# loom-charging-cart.net
KiCad netlist of a schematic drawn in Altium Designer
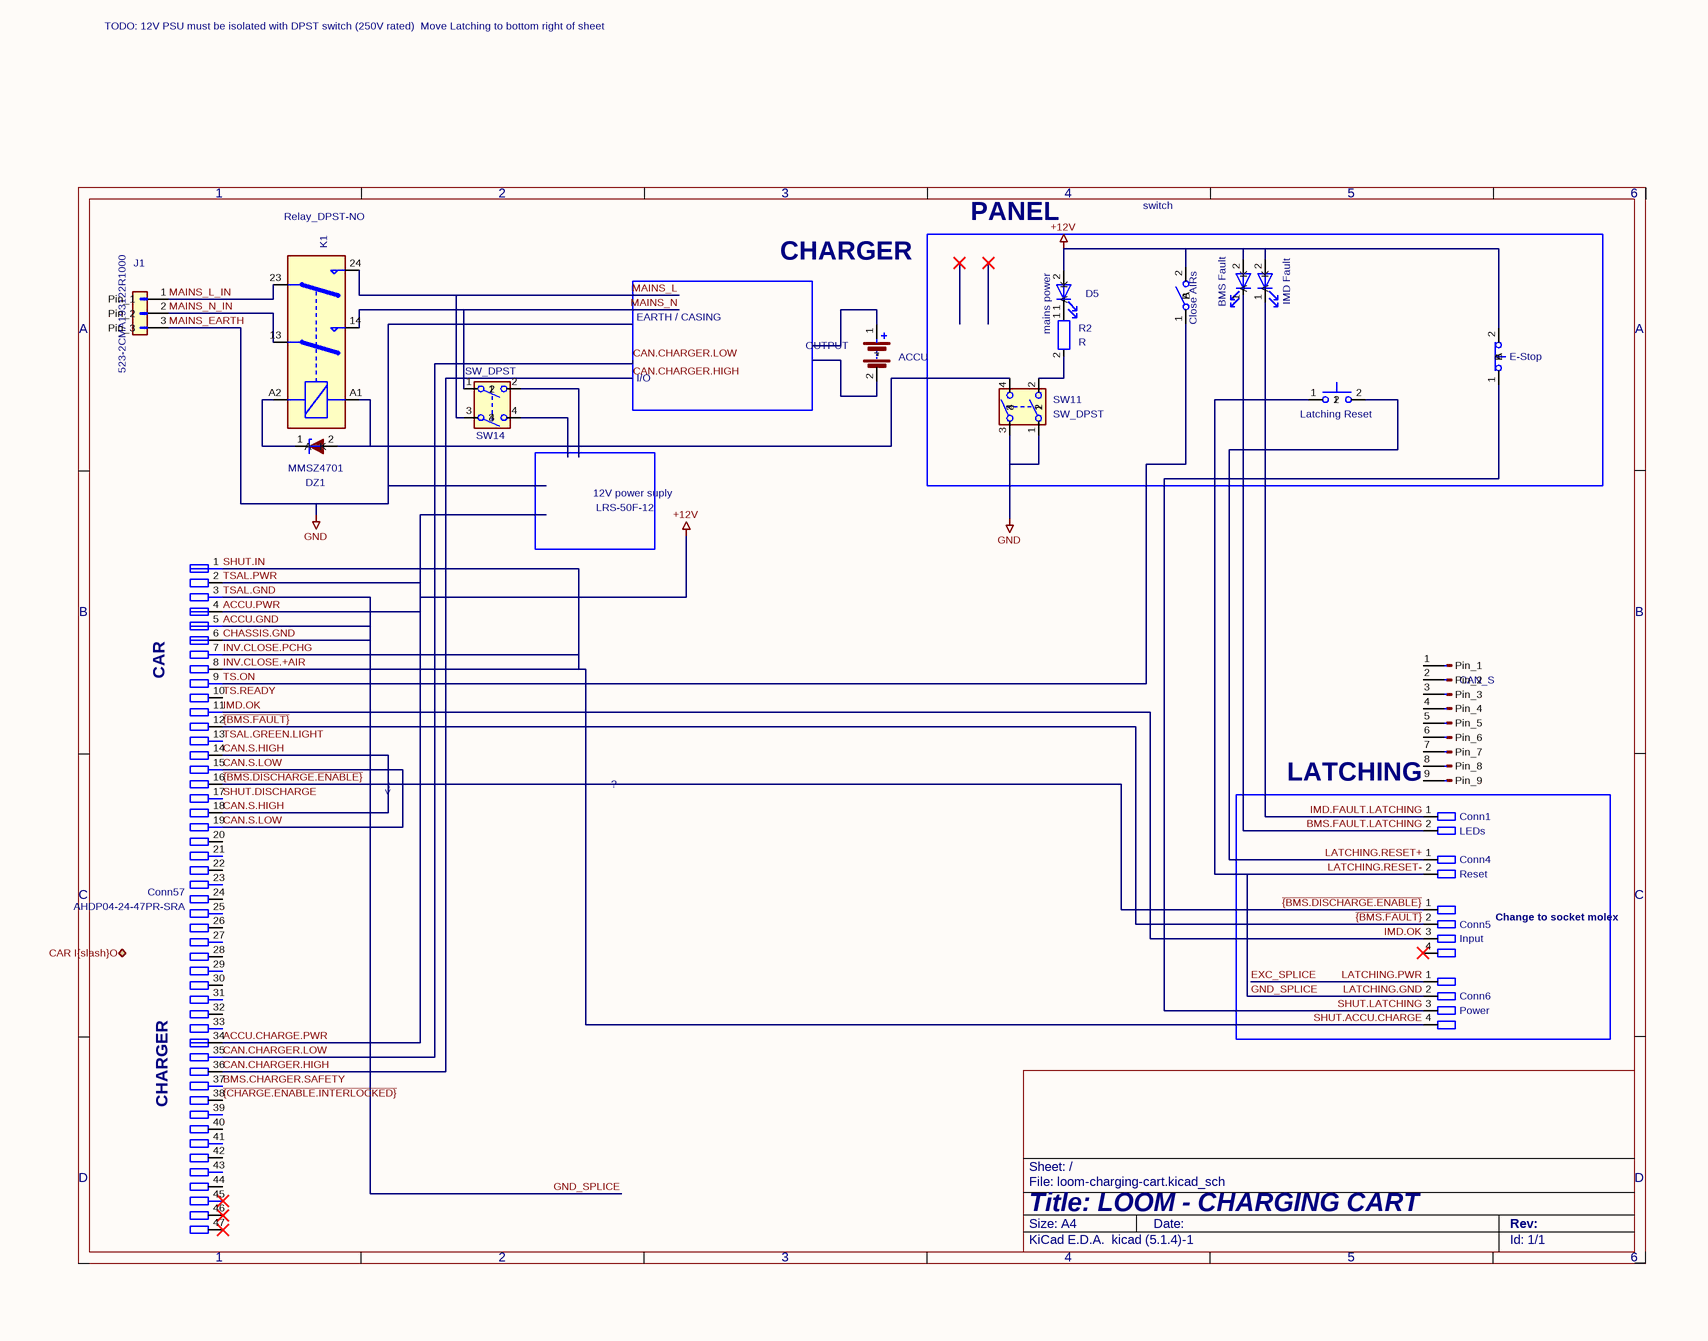
[diagram p0: loom-charging-cart.SchDoc]

(export (version "E")
  (design (tool "Eeschema 10.0.6"))
  (components
    (comp (ref "BT1")
      (value "ACCU")
      (description "Multiple-cell battery")
      (libsource (lib "Device") (part "Battery"))
    )
    (comp (ref "Conn1")
      (value "Molex_2x1P_Horizontal_THT")
      (fields (field (name "NAME") "LEDs"))
      (libsource (lib "Connectors_SUFST") (part "Molex_2x1P_Horizontal_THT"))
    )
    (comp (ref "Conn4")
      (value "Molex_2x1P_Horizontal_THT")
      (fields (field (name "NAME") "Reset"))
      (libsource (lib "Connectors_SUFST") (part "Molex_2x1P_Horizontal_THT"))
    )
    (comp (ref "Conn5")
      (value "Molex_2x2P_Horizontal")
      (fields (field (name "NAME") "Input"))
      (libsource (lib "Connectors_SUFST") (part "Molex_2x2P_Horizontal"))
    )
    (comp (ref "Conn6")
      (value "Molex_2x2P_Horizontal")
      (fields (field (name "NAME") "Power"))
      (libsource (lib "Connectors_SUFST") (part "Molex_2x2P_Horizontal"))
    )
    (comp (ref "Conn57")
      (value "AMPHENOL-47P-Pannel")
      (fields (field (name "P/N") "AHDP04-24-47PR-SRA"))
      (libsource (lib "Connectors_SUFST") (part "AMPHENOL-47P-Pannel"))
    )
    (comp (ref "D1")
      (value "IMD Fault")
      (description "Light emitting diode")
      (libsource (lib "Device") (part "LED"))
    )
    (comp (ref "D2")
      (value "BMS Fault")
      (description "Light emitting diode")
      (libsource (lib "Device") (part "LED"))
    )
    (comp (ref "D5")
      (value "mains power")
      (description "Light emitting diode")
      (libsource (lib "*") (part "LED_1"))
    )
    (comp (ref "DZ1")
      (value "MMSZ4701")
      (footprint "D_SOD-123")
      (description "SOD-123 Zener diode, 14V, 500mW, Alternate KiCAD Library")
      (libsource (lib "PCM_Diode_Zener_AKL") (part "MMSZ4701"))
    )
    (comp (ref "J1") (value "523-2CMA193122R1000") (libsource (lib "Connector_Generic") (part "Conn_01x03")))
    (comp (ref "J2")
      (value "CAN_S")
      (description "Generic connector, single row, 01x09, script generated")
      (libsource (lib "Connector") (part "Conn_01x09_Pin"))
    )
    (comp (ref "K1")
      (value "Relay_DPST-NO")
      (description "Monostable Relay DPST, Normally Open, EN50005")
      (libsource (lib "Relay") (part "Relay_DPST-NO"))
    )
    (comp (ref "R2") (value "R") (description "Resistor") (libsource (lib "Device") (part "R")))
    (comp (ref "SW1") (value "E-Stop") (libsource (lib "Switch") (part "SW_Push_Open")))
    (comp (ref "SW2")
      (value "Latching Reset")
      (description "Push button switch, generic, two pins")
      (libsource (lib "Switch") (part "SW_Push"))
    )
    (comp (ref "SW3")
      (value "Close AIRs")
      (description "Single Pole Single Throw (SPST) switch")
      (libsource (lib "Switch") (part "SW_SPST"))
    )
    (comp (ref "SW11")
      (value "SW_DPST")
      (description "Double Pole Single Throw (DPST) Switch")
      (libsource (lib "Switch") (part "SW_DPST"))
    )
    (comp (ref "SW14")
      (value "SW_DPST")
      (description "Double Pole Single Throw (DPST) Switch")
      (libsource (lib "Switch") (part "SW_DPST"))
    )
  )
  (nets
    (net (code "1") (name "+12V") (class "Default")
      (node (ref "Conn57") (pin "2") (pinfunction "2_2") (pintype "passive"))
      (node (ref "Conn57") (pin "34") (pinfunction "34_34") (pintype "passive"))
      (node (ref "Conn57") (pin "4") (pinfunction "4_4") (pintype "passive"))
      (node (ref "D1") (pin "2") (pinfunction "A_2") (pintype "passive"))
      (node (ref "D2") (pin "2") (pinfunction "A_2") (pintype "passive"))
      (node (ref "D5") (pin "2") (pinfunction "A_2") (pintype "passive"))
      (node (ref "SW1") (pin "2") (pinfunction "B_2") (pintype "passive"))
      (node (ref "SW3") (pin "2") (pinfunction "B_2") (pintype "passive"))
    )
    (net (code "2") (name "/ACCU.GND") (class "Default")
      (node (ref "Conn4") (pin "2") (pinfunction "2_2") (pintype "passive"))
      (node (ref "Conn57") (pin "3") (pinfunction "3_3") (pintype "passive"))
      (node (ref "Conn57") (pin "5") (pinfunction "5_5") (pintype "passive"))
      (node (ref "Conn57") (pin "6") (pinfunction "6_6") (pintype "passive"))
      (node (ref "Conn6") (pin "2") (pinfunction "2_2") (pintype "passive"))
      (node (ref "SW2") (pin "1") (pinfunction "1_1") (pintype "passive"))
    )
    (net (code "3") (name "/BMS.CHARGER.SAFETY") (class "Default")
      (node (ref "Conn57") (pin "37") (pinfunction "37_37") (pintype "passive"))
    )
    (net (code "4") (name "/BMS.FAULT.LATCHING") (class "Default")
      (node (ref "Conn1") (pin "2") (pinfunction "2_2") (pintype "passive"))
      (node (ref "D2") (pin "1") (pinfunction "K_1") (pintype "passive"))
    )
    (net (code "5") (name "/CAN.CHARGER.HIGH") (class "Default")
      (node (ref "Conn57") (pin "36") (pinfunction "36_36") (pintype "passive"))
    )
    (net (code "6") (name "/CAN.CHARGER.LOW") (class "Default")
      (node (ref "Conn57") (pin "35") (pinfunction "35_35") (pintype "passive"))
    )
    (net (code "7") (name "/CAN.S.HIGH") (class "Default")
      (node (ref "Conn57") (pin "14") (pinfunction "14_14") (pintype "passive"))
      (node (ref "Conn57") (pin "18") (pinfunction "18_18") (pintype "passive"))
    )
    (net (code "8") (name "/CAN.S.LOW") (class "Default")
      (node (ref "Conn57") (pin "15") (pinfunction "15_15") (pintype "passive"))
      (node (ref "Conn57") (pin "19") (pinfunction "19_19") (pintype "passive"))
    )
    (net (code "10") (name "/EXC_SPLICE") (class "Default")
      (node (ref "Conn6") (pin "1") (pinfunction "1_1") (pintype "passive"))
    )
    (net (code "11") (name "/IMD.FAULT.LATCHING") (class "Default")
      (node (ref "Conn1") (pin "1") (pinfunction "1_1") (pintype "passive"))
      (node (ref "D1") (pin "1") (pinfunction "K_1") (pintype "passive"))
    )
    (net (code "12") (name "/IMD.OK") (class "Default")
      (node (ref "Conn5") (pin "3") (pinfunction "3_3") (pintype "passive"))
      (node (ref "Conn57") (pin "11") (pinfunction "11_11") (pintype "passive"))
    )
    (net (code "13") (name "/INV.CLOSE.+AIR") (class "Default")
      (node (ref "Conn57") (pin "1") (pinfunction "1_1") (pintype "passive"))
      (node (ref "Conn57") (pin "7") (pinfunction "7_7") (pintype "passive"))
      (node (ref "Conn57") (pin "8") (pinfunction "8_8") (pintype "passive"))
      (node (ref "Conn6") (pin "4") (pinfunction "4_4") (pintype "passive"))
    )
    (net (code "14") (name "/LATCHING.RESET+") (class "Default")
      (node (ref "Conn4") (pin "1") (pinfunction "1_1") (pintype "passive"))
      (node (ref "SW2") (pin "2") (pinfunction "2_2") (pintype "passive"))
    )
    (net (code "15") (name "/MAINS_L") (class "Default")
      (node (ref "K1") (pin "24") (pinfunction "24_24") (pintype "passive"))
      (node (ref "SW14") (pin "3") (pinfunction "3_3") (pintype "passive"))
    )
    (net (code "16") (name "/MAINS_L_IN") (class "Default")
      (node (ref "J1") (pin "1") (pinfunction "Pin_1_1") (pintype "passive"))
      (node (ref "K1") (pin "23") (pinfunction "23_23") (pintype "passive"))
    )
    (net (code "17") (name "/MAINS_N") (class "Default")
      (node (ref "K1") (pin "14") (pinfunction "14_14") (pintype "passive"))
      (node (ref "SW14") (pin "1") (pinfunction "1_1") (pintype "passive"))
    )
    (net (code "18") (name "/MAINS_N_IN") (class "Default")
      (node (ref "J1") (pin "2") (pinfunction "Pin_2_2") (pintype "passive"))
      (node (ref "K1") (pin "13") (pinfunction "13_13") (pintype "passive"))
    )
    (net (code "19") (name "/SHUT.DISCHARGE") (class "Default")
      (node (ref "Conn57") (pin "17") (pinfunction "17_17") (pintype "passive"))
    )
    (net (code "20") (name "/SHUT.LATCHING") (class "Default")
      (node (ref "Conn6") (pin "3") (pinfunction "3_3") (pintype "passive"))
      (node (ref "SW1") (pin "1") (pinfunction "A_1") (pintype "passive"))
    )
    (net (code "21") (name "/TS.ON") (class "Default")
      (node (ref "Conn57") (pin "9") (pinfunction "9_9") (pintype "passive"))
      (node (ref "SW3") (pin "1") (pinfunction "A_1") (pintype "passive"))
    )
    (net (code "22") (name "/TS.READY") (class "Default")
      (node (ref "Conn57") (pin "10") (pinfunction "10_10") (pintype "passive"))
    )
    (net (code "23") (name "/TSAL.GREEN.LIGHT") (class "Default")
      (node (ref "Conn57") (pin "13") (pinfunction "13_13") (pintype "passive"))
    )
    (net (code "24") (name "/~{{BMS.DISCHARGE.ENABLE}}") (class "Default")
      (node (ref "Conn5") (pin "1") (pinfunction "1_1") (pintype "passive"))
      (node (ref "Conn57") (pin "16") (pinfunction "16_16") (pintype "passive"))
    )
    (net (code "25") (name "/~{{BMS.FAULT}}") (class "Default")
      (node (ref "Conn5") (pin "2") (pinfunction "2_2") (pintype "passive"))
      (node (ref "Conn57") (pin "12") (pinfunction "12_12") (pintype "passive"))
    )
    (net (code "26") (name "/~{{CHARGE.ENABLE.INTERLOCKED}}") (class "Default")
      (node (ref "Conn57") (pin "38") (pinfunction "38_38") (pintype "passive"))
    )
    (net (code "27") (name "GND") (class "Default")
      (node (ref "J1") (pin "3") (pinfunction "Pin_3_3") (pintype "passive"))
      (node (ref "SW11") (pin "1") (pinfunction "1_1") (pintype "passive"))
      (node (ref "SW11") (pin "3") (pinfunction "3_3") (pintype "passive"))
    )
    (net (code "28") (name "Net-(D5-K)") (class "Default")
      (node (ref "D5") (pin "1") (pinfunction "K_1") (pintype "passive"))
      (node (ref "R2") (pin "1") (pinfunction "1_1") (pintype "passive"))
    )
    (net (code "29") (name "Net-(DZ1-A)") (class "Default")
      (node (ref "DZ1") (pin "2") (pinfunction "A_2") (pintype "passive"))
      (node (ref "K1") (pin "A1") (pinfunction "A1_A1") (pintype "passive"))
      (node (ref "SW11") (pin "4") (pinfunction "4_4") (pintype "passive"))
    )
    (net (code "30") (name "Net-(DZ1-K)") (class "Default")
      (node (ref "DZ1") (pin "1") (pinfunction "K_1") (pintype "passive"))
      (node (ref "K1") (pin "A2") (pinfunction "A2_A2") (pintype "passive"))
    )
    (net (code "31") (name "Net-(R2-Pad2)") (class "Default")
      (node (ref "R2") (pin "2") (pinfunction "2_2") (pintype "passive"))
      (node (ref "SW11") (pin "2") (pinfunction "2_2") (pintype "passive"))
    )
    (net (code "32") (name "unconnected-(BT1-+-Pad1)") (class "Default")
      (node (ref "BT1") (pin "1") (pinfunction "+_1") (pintype "passive"))
    )
    (net (code "33") (name "unconnected-(BT1---Pad2)") (class "Default")
      (node (ref "BT1") (pin "2") (pinfunction "-_2") (pintype "passive"))
    )
    (net (code "34") (name "unconnected-(Conn5-Pad4)") (class "Default")
      (node (ref "Conn5") (pin "4") (pinfunction "4_4") (pintype "passive+no_connect"))
    )
    (net (code "35") (name "unconnected-(Conn57-Pad20)") (class "Default")
      (node (ref "Conn57") (pin "20") (pinfunction "20_20") (pintype "passive"))
    )
    (net (code "36") (name "unconnected-(Conn57-Pad21)") (class "Default")
      (node (ref "Conn57") (pin "21") (pinfunction "21_21") (pintype "passive"))
    )
    (net (code "37") (name "unconnected-(Conn57-Pad22)") (class "Default")
      (node (ref "Conn57") (pin "22") (pinfunction "22_22") (pintype "passive"))
    )
    (net (code "38") (name "unconnected-(Conn57-Pad23)") (class "Default")
      (node (ref "Conn57") (pin "23") (pinfunction "23_23") (pintype "passive"))
    )
    (net (code "39") (name "unconnected-(Conn57-Pad24)") (class "Default")
      (node (ref "Conn57") (pin "24") (pinfunction "24_24") (pintype "passive"))
    )
    (net (code "40") (name "unconnected-(Conn57-Pad25)") (class "Default")
      (node (ref "Conn57") (pin "25") (pinfunction "25_25") (pintype "passive"))
    )
    (net (code "41") (name "unconnected-(Conn57-Pad26)") (class "Default")
      (node (ref "Conn57") (pin "26") (pinfunction "26_26") (pintype "passive"))
    )
    (net (code "42") (name "unconnected-(Conn57-Pad27)") (class "Default")
      (node (ref "Conn57") (pin "27") (pinfunction "27_27") (pintype "passive"))
    )
    (net (code "43") (name "unconnected-(Conn57-Pad28)") (class "Default")
      (node (ref "Conn57") (pin "28") (pinfunction "28_28") (pintype "passive"))
    )
    (net (code "44") (name "unconnected-(Conn57-Pad29)") (class "Default")
      (node (ref "Conn57") (pin "29") (pinfunction "29_29") (pintype "passive"))
    )
    (net (code "45") (name "unconnected-(Conn57-Pad30)") (class "Default")
      (node (ref "Conn57") (pin "30") (pinfunction "30_30") (pintype "passive"))
    )
    (net (code "46") (name "unconnected-(Conn57-Pad31)") (class "Default")
      (node (ref "Conn57") (pin "31") (pinfunction "31_31") (pintype "passive"))
    )
    (net (code "47") (name "unconnected-(Conn57-Pad32)") (class "Default")
      (node (ref "Conn57") (pin "32") (pinfunction "32_32") (pintype "passive"))
    )
    (net (code "48") (name "unconnected-(Conn57-Pad33)") (class "Default")
      (node (ref "Conn57") (pin "33") (pinfunction "33_33") (pintype "passive"))
    )
    (net (code "49") (name "unconnected-(Conn57-Pad39)") (class "Default")
      (node (ref "Conn57") (pin "39") (pinfunction "39_39") (pintype "passive"))
    )
    (net (code "50") (name "unconnected-(Conn57-Pad40)") (class "Default")
      (node (ref "Conn57") (pin "40") (pinfunction "40_40") (pintype "passive"))
    )
    (net (code "51") (name "unconnected-(Conn57-Pad41)") (class "Default")
      (node (ref "Conn57") (pin "41") (pinfunction "41_41") (pintype "passive"))
    )
    (net (code "52") (name "unconnected-(Conn57-Pad42)") (class "Default")
      (node (ref "Conn57") (pin "42") (pinfunction "42_42") (pintype "passive"))
    )
    (net (code "53") (name "unconnected-(Conn57-Pad43)") (class "Default")
      (node (ref "Conn57") (pin "43") (pinfunction "43_43") (pintype "passive"))
    )
    (net (code "54") (name "unconnected-(Conn57-Pad44)") (class "Default")
      (node (ref "Conn57") (pin "44") (pinfunction "44_44") (pintype "passive"))
    )
    (net (code "55") (name "unconnected-(Conn57-Pad45)") (class "Default")
      (node (ref "Conn57") (pin "45") (pinfunction "45_45") (pintype "passive+no_connect"))
    )
    (net (code "56") (name "unconnected-(Conn57-Pad46)") (class "Default")
      (node (ref "Conn57") (pin "46") (pinfunction "46_46") (pintype "passive+no_connect"))
    )
    (net (code "57") (name "unconnected-(Conn57-Pad47)") (class "Default")
      (node (ref "Conn57") (pin "47") (pinfunction "47_47") (pintype "passive+no_connect"))
    )
    (net (code "58") (name "unconnected-(J2-Pin_1-Pad1)") (class "Default")
      (node (ref "J2") (pin "1") (pinfunction "Pin_1_1") (pintype "passive"))
    )
    (net (code "59") (name "unconnected-(J2-Pin_2-Pad2)") (class "Default")
      (node (ref "J2") (pin "2") (pinfunction "Pin_2_2") (pintype "passive"))
    )
    (net (code "60") (name "unconnected-(J2-Pin_3-Pad3)") (class "Default")
      (node (ref "J2") (pin "3") (pinfunction "Pin_3_3") (pintype "passive"))
    )
    (net (code "61") (name "unconnected-(J2-Pin_4-Pad4)") (class "Default")
      (node (ref "J2") (pin "4") (pinfunction "Pin_4_4") (pintype "passive"))
    )
    (net (code "62") (name "unconnected-(J2-Pin_5-Pad5)") (class "Default")
      (node (ref "J2") (pin "5") (pinfunction "Pin_5_5") (pintype "passive"))
    )
    (net (code "63") (name "unconnected-(J2-Pin_6-Pad6)") (class "Default")
      (node (ref "J2") (pin "6") (pinfunction "Pin_6_6") (pintype "passive"))
    )
    (net (code "64") (name "unconnected-(J2-Pin_7-Pad7)") (class "Default")
      (node (ref "J2") (pin "7") (pinfunction "Pin_7_7") (pintype "passive"))
    )
    (net (code "65") (name "unconnected-(J2-Pin_8-Pad8)") (class "Default")
      (node (ref "J2") (pin "8") (pinfunction "Pin_8_8") (pintype "passive"))
    )
    (net (code "66") (name "unconnected-(J2-Pin_9-Pad9)") (class "Default")
      (node (ref "J2") (pin "9") (pinfunction "Pin_9_9") (pintype "passive"))
    )
    (net (code "67") (name "unconnected-(SW14-Pad2)") (class "Default")
      (node (ref "SW14") (pin "2") (pinfunction "2_2") (pintype "passive"))
    )
    (net (code "68") (name "unconnected-(SW14-Pad4)") (class "Default")
      (node (ref "SW14") (pin "4") (pinfunction "4_4") (pintype "passive"))
    )
  )
)
